# 02_IO.net
KiCad netlist of a schematic drawn in Altium Designer
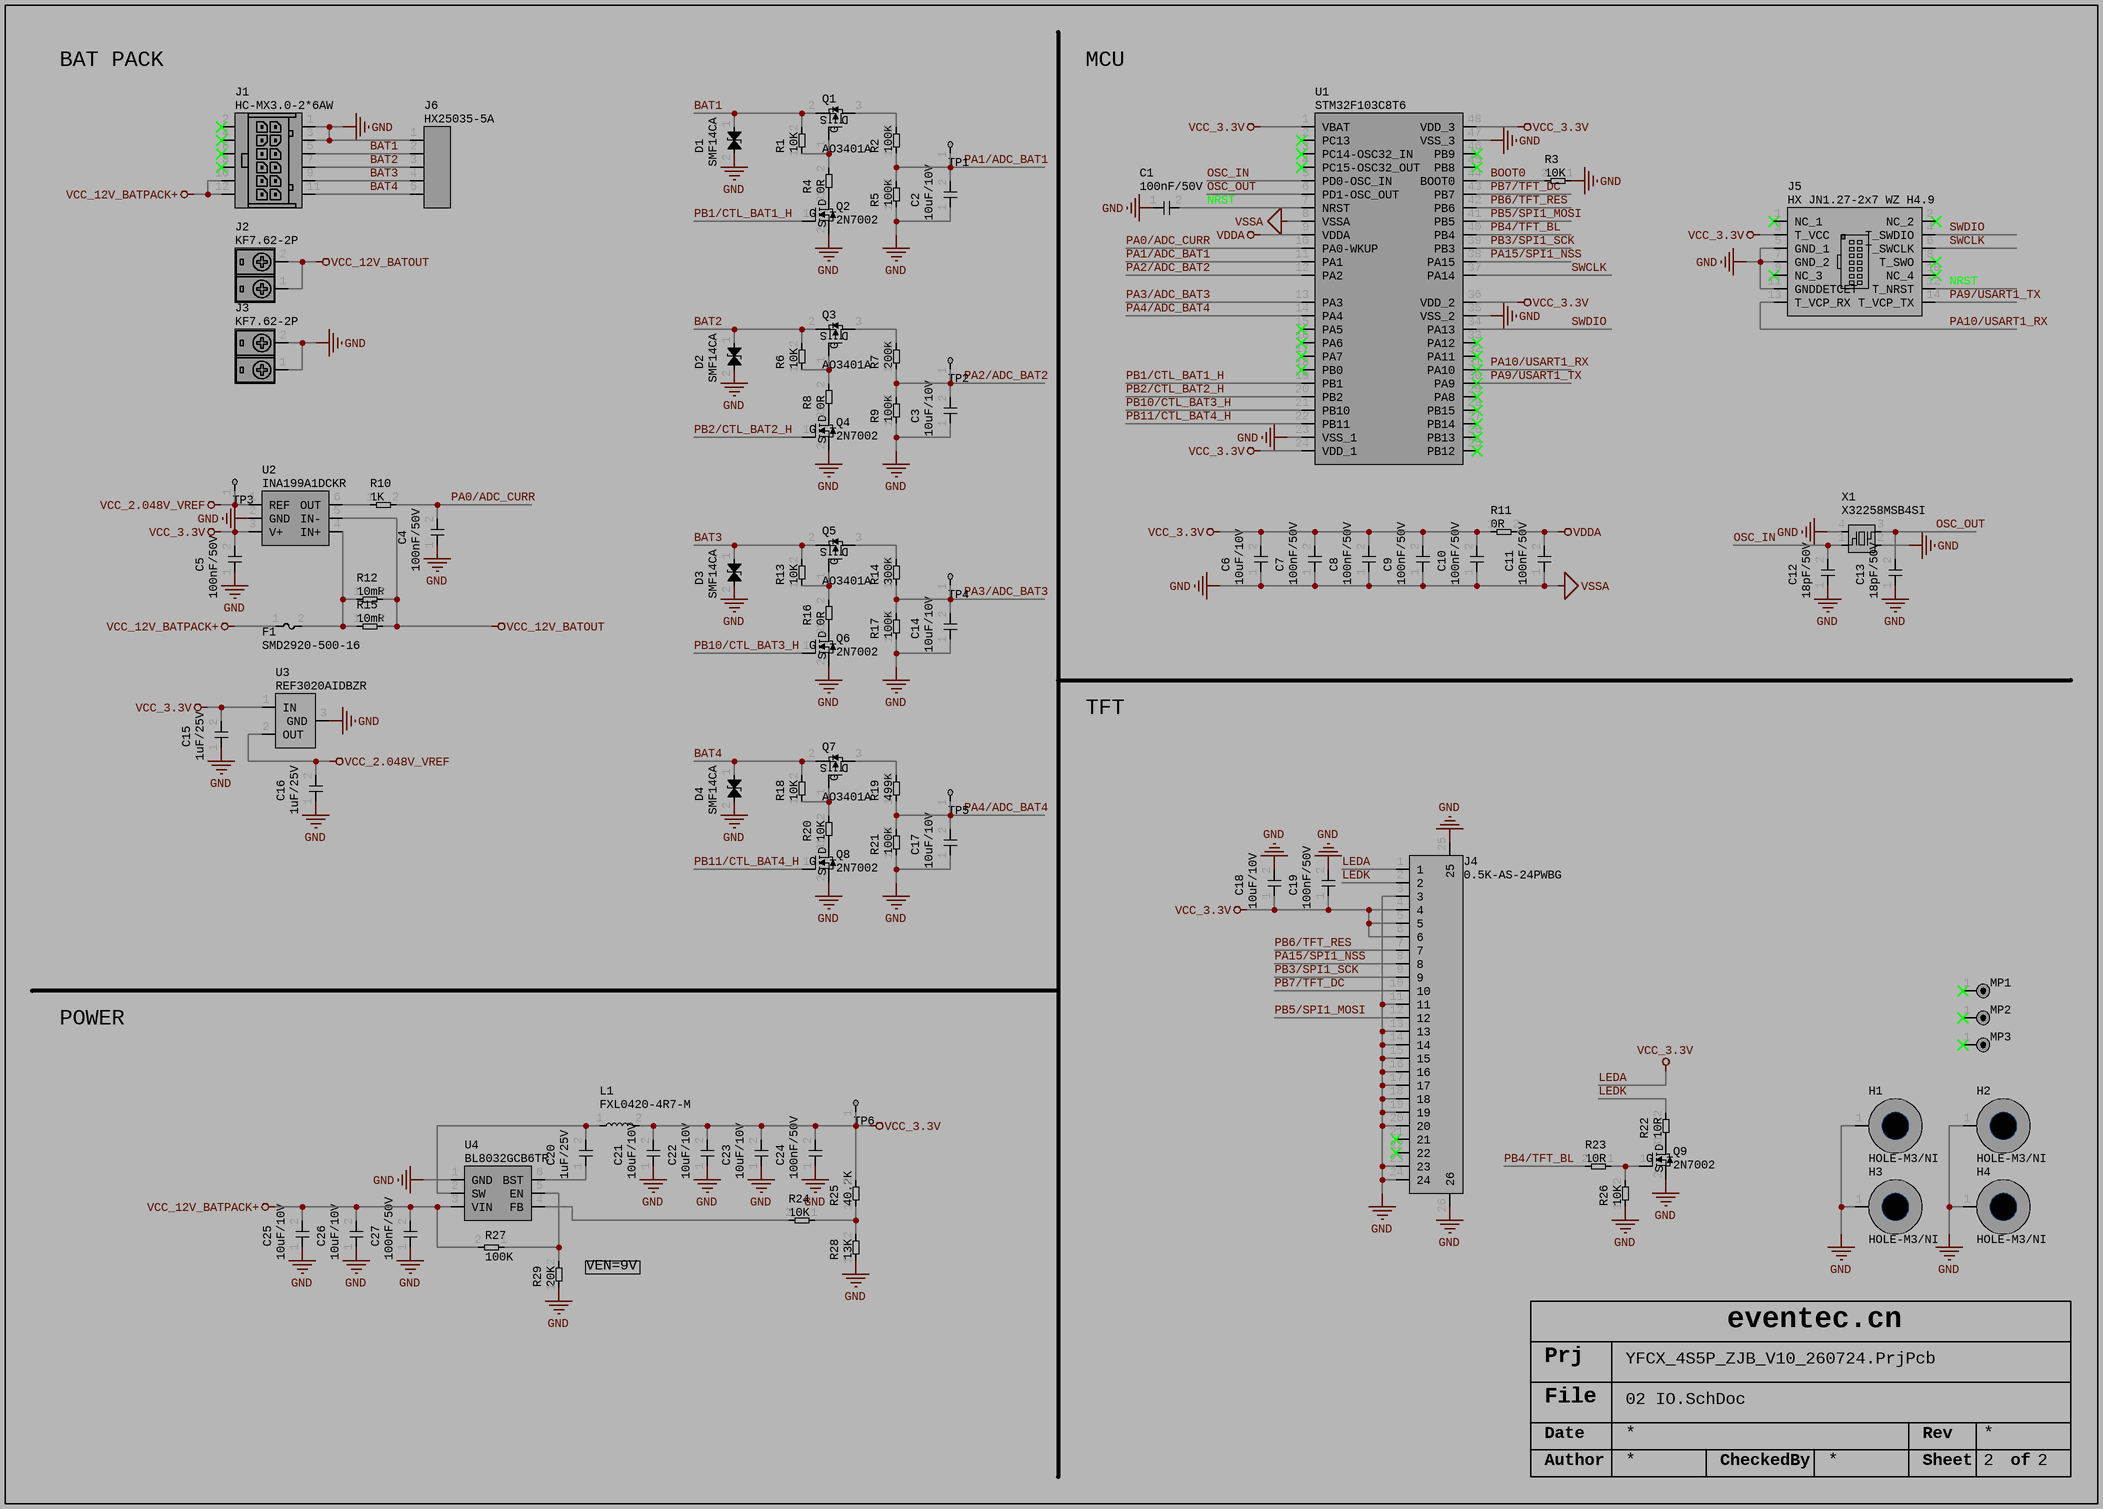
[diagram p0: 02 IO.SchDoc]

(export (version "E")
  (design (tool "Eeschema 10.0.6"))
  (components
    (comp (ref "C1") (value "100nF/50V") (footprint "C0402") (libsource (lib "YFCX") (part "100nF/50V")))
    (comp (ref "C2") (value "10uF/10V") (footprint "C0603") (libsource (lib "YFCX") (part "100nF/50V")))
    (comp (ref "C3") (value "10uF/10V") (footprint "C0603") (libsource (lib "YFCX") (part "100nF/50V")))
    (comp (ref "C4") (value "100nF/50V") (footprint "C0402") (libsource (lib "YFCX") (part "100nF/50V")))
    (comp (ref "C5") (value "100nF/50V") (footprint "C0402") (libsource (lib "YFCX") (part "100nF/50V")))
    (comp (ref "C6") (value "10uF/10V") (footprint "C0603") (libsource (lib "YFCX") (part "100nF/50V")))
    (comp (ref "C7") (value "100nF/50V") (footprint "C0402") (libsource (lib "YFCX") (part "100nF/50V")))
    (comp (ref "C8") (value "100nF/50V") (footprint "C0402") (libsource (lib "YFCX") (part "100nF/50V")))
    (comp (ref "C9") (value "100nF/50V") (footprint "C0402") (libsource (lib "YFCX") (part "100nF/50V")))
    (comp (ref "C10") (value "100nF/50V") (footprint "C0402") (libsource (lib "YFCX") (part "100nF/50V")))
    (comp (ref "C11") (value "100nF/50V") (footprint "C0402") (libsource (lib "YFCX") (part "100nF/50V")))
    (comp (ref "C12") (value "18pF/50V") (footprint "C0402") (libsource (lib "YFCX") (part "100nF/50V")))
    (comp (ref "C13") (value "18pF/50V") (footprint "C0402") (libsource (lib "YFCX") (part "100nF/50V")))
    (comp (ref "C14") (value "10uF/10V") (footprint "C0603") (libsource (lib "YFCX") (part "100nF/50V")))
    (comp (ref "C15") (value "1uF/25V") (footprint "C0402") (libsource (lib "YFCX") (part "100nF/50V")))
    (comp (ref "C16") (value "1uF/25V") (footprint "C0402") (libsource (lib "YFCX") (part "100nF/50V")))
    (comp (ref "C17") (value "10uF/10V") (footprint "C0603") (libsource (lib "YFCX") (part "100nF/50V")))
    (comp (ref "C18") (value "10uF/10V") (footprint "C0603") (libsource (lib "YFCX") (part "100nF/50V")))
    (comp (ref "C19") (value "100nF/50V") (footprint "C0402") (libsource (lib "YFCX") (part "100nF/50V")))
    (comp (ref "C20") (value "1uF/25V") (footprint "C0402") (libsource (lib "YFCX") (part "100nF/50V")))
    (comp (ref "C21") (value "10uF/10V") (footprint "C0603") (libsource (lib "YFCX") (part "100nF/50V")))
    (comp (ref "C22") (value "10uF/10V") (footprint "C0603") (libsource (lib "YFCX") (part "100nF/50V")))
    (comp (ref "C23") (value "10uF/10V") (footprint "C0603") (libsource (lib "YFCX") (part "100nF/50V")))
    (comp (ref "C24") (value "100nF/50V") (footprint "C0402") (libsource (lib "YFCX") (part "100nF/50V")))
    (comp (ref "C25") (value "10uF/10V") (footprint "C0603") (libsource (lib "YFCX") (part "100nF/50V")))
    (comp (ref "C26") (value "10uF/10V") (footprint "C0603") (libsource (lib "YFCX") (part "100nF/50V")))
    (comp (ref "C27") (value "100nF/50V") (footprint "C0402") (libsource (lib "YFCX") (part "100nF/50V")))
    (comp (ref "D1") (value "SMF14CA") (footprint "SOD123") (libsource (lib "YFCX") (part "TVS-BDIR")))
    (comp (ref "D2") (value "SMF14CA") (footprint "SOD123") (libsource (lib "YFCX") (part "TVS-BDIR")))
    (comp (ref "D3") (value "SMF14CA") (footprint "SOD123") (libsource (lib "YFCX") (part "TVS-BDIR")))
    (comp (ref "D4") (value "SMF14CA") (footprint "SOD123") (libsource (lib "YFCX") (part "TVS-BDIR")))
    (comp (ref "F1") (value "SMD2920-500-16") (footprint "FUSE2920") (libsource (lib "YFCX") (part "FUSE")))
    (comp (ref "H1")
      (value "HOLE-M3/NI")
      (footprint "HOLE6R90X3R10")
      (libsource (lib "YFCX") (part "HOLE-M3"))
    )
    (comp (ref "H2")
      (value "HOLE-M3/NI")
      (footprint "HOLE6R90X3R10")
      (libsource (lib "YFCX") (part "HOLE-M3"))
    )
    (comp (ref "H3")
      (value "HOLE-M3/NI")
      (footprint "HOLE6R90X3R10")
      (libsource (lib "YFCX") (part "HOLE-M3"))
    )
    (comp (ref "H4")
      (value "HOLE-M3/NI")
      (footprint "HOLE6R90X3R10")
      (libsource (lib "YFCX") (part "HOLE-M3"))
    )
    (comp (ref "J1")
      (value "HC-MX3.0-2*6AW")
      (footprint "HC-MX3R0-2X6AW")
      (libsource (lib "YFCX") (part "HC-MX3.0-2*6AW"))
    )
    (comp (ref "J2") (value "KF7.62-2P") (footprint "KF7R62-2P") (libsource (lib "YFCX") (part "KF7.62-2P")))
    (comp (ref "J3") (value "KF7.62-2P") (footprint "KF7R62-2P") (libsource (lib "YFCX") (part "KF7.62-2P")))
    (comp (ref "J4")
      (value "0.5K-AS-24PWBG")
      (footprint "0R5K-AS-24PWBG")
      (libsource (lib "YFCX") (part "0.5K-AS-24PWBG"))
    )
    (comp (ref "J5")
      (value "HX JN1.27-2x7 WZ H4.9")
      (footprint "STDC14-W")
      (libsource (lib "YFCX") (part "STDC14"))
    )
    (comp (ref "J6")
      (value "HX25035-5A")
      (footprint "HX25035-5A")
      (libsource (lib "YFCX") (part "HX25035-5A"))
    )
    (comp (ref "L1") (value "FXL0420-4R7-M") (footprint "L0420") (libsource (lib "YFCX") (part "INDUC")))
    (comp (ref "MP1") (value "MARK-R3/NI") (footprint "MARK-R3") (libsource (lib "YFCX") (part "MARK-R3")))
    (comp (ref "MP2") (value "MARK-R3/NI") (footprint "MARK-R3") (libsource (lib "YFCX") (part "MARK-R3")))
    (comp (ref "MP3") (value "MARK-R3/NI") (footprint "MARK-R3") (libsource (lib "YFCX") (part "MARK-R3")))
    (comp (ref "Q1") (value "AO3401A") (footprint "SOT23-3") (libsource (lib "YFCX") (part "MOS-P")))
    (comp (ref "Q2") (value "2N7002") (footprint "SOT23-3") (libsource (lib "YFCX") (part "MOS-N")))
    (comp (ref "Q3") (value "AO3401A") (footprint "SOT23-3") (libsource (lib "YFCX") (part "MOS-P")))
    (comp (ref "Q4") (value "2N7002") (footprint "SOT23-3") (libsource (lib "YFCX") (part "MOS-N")))
    (comp (ref "Q5") (value "AO3401A") (footprint "SOT23-3") (libsource (lib "YFCX") (part "MOS-P")))
    (comp (ref "Q6") (value "2N7002") (footprint "SOT23-3") (libsource (lib "YFCX") (part "MOS-N")))
    (comp (ref "Q7") (value "AO3401A") (footprint "SOT23-3") (libsource (lib "YFCX") (part "MOS-P")))
    (comp (ref "Q8") (value "2N7002") (footprint "SOT23-3") (libsource (lib "YFCX") (part "MOS-N")))
    (comp (ref "Q9") (value "2N7002") (footprint "SOT23-3") (libsource (lib "YFCX") (part "MOS-N")))
    (comp (ref "R1") (value "10K") (footprint "R0402") (libsource (lib "YFCX") (part "1K")))
    (comp (ref "R2") (value "100K") (footprint "R0402") (libsource (lib "YFCX") (part "1K")))
    (comp (ref "R3") (value "10K") (footprint "R0402") (libsource (lib "YFCX") (part "1K")))
    (comp (ref "R4") (value "0R") (footprint "R0402") (libsource (lib "YFCX") (part "1K")))
    (comp (ref "R5") (value "100K") (footprint "R0402") (libsource (lib "YFCX") (part "1K")))
    (comp (ref "R6") (value "10K") (footprint "R0402") (libsource (lib "YFCX") (part "1K")))
    (comp (ref "R7") (value "200K") (footprint "R0402") (libsource (lib "YFCX") (part "1K")))
    (comp (ref "R8") (value "0R") (footprint "R0402") (libsource (lib "YFCX") (part "1K")))
    (comp (ref "R9") (value "100K") (footprint "R0402") (libsource (lib "YFCX") (part "1K")))
    (comp (ref "R10") (value "1K") (footprint "R0402") (libsource (lib "YFCX") (part "1K")))
    (comp (ref "R11") (value "0R") (footprint "R0402") (libsource (lib "YFCX") (part "1K")))
    (comp (ref "R12") (value "10mR") (footprint "R2512") (libsource (lib "YFCX") (part "1K")))
    (comp (ref "R13") (value "10K") (footprint "R0402") (libsource (lib "YFCX") (part "1K")))
    (comp (ref "R14") (value "300K") (footprint "R0402") (libsource (lib "YFCX") (part "1K")))
    (comp (ref "R15") (value "10mR") (footprint "R2512") (libsource (lib "YFCX") (part "1K")))
    (comp (ref "R16") (value "0R") (footprint "R0402") (libsource (lib "YFCX") (part "1K")))
    (comp (ref "R17") (value "100K") (footprint "R0402") (libsource (lib "YFCX") (part "1K")))
    (comp (ref "R18") (value "10K") (footprint "R0402") (libsource (lib "YFCX") (part "1K")))
    (comp (ref "R19") (value "499K") (footprint "R0402") (libsource (lib "YFCX") (part "1K")))
    (comp (ref "R20") (value "10K") (footprint "R0402") (libsource (lib "YFCX") (part "1K")))
    (comp (ref "R21") (value "100K") (footprint "R0402") (libsource (lib "YFCX") (part "1K")))
    (comp (ref "R22") (value "10R") (footprint "R0805") (libsource (lib "YFCX") (part "1K")))
    (comp (ref "R23") (value "10R") (footprint "R0805") (libsource (lib "YFCX") (part "1K")))
    (comp (ref "R24") (value "10K") (footprint "R0402") (libsource (lib "YFCX") (part "1K")))
    (comp (ref "R25") (value "40.2K") (footprint "R0402") (libsource (lib "YFCX") (part "1K")))
    (comp (ref "R26") (value "10K") (footprint "R0402") (libsource (lib "YFCX") (part "1K")))
    (comp (ref "R27") (value "100K") (footprint "R0402") (libsource (lib "YFCX") (part "1K")))
    (comp (ref "R28") (value "13K") (footprint "R0402") (libsource (lib "YFCX") (part "1K")))
    (comp (ref "R29") (value "20K") (footprint "R0402") (libsource (lib "YFCX") (part "1K")))
    (comp (ref "TP1") (value "TP-R2/NI") (footprint "TP-R2") (libsource (lib "YFCX") (part "TP-R2")))
    (comp (ref "TP2") (value "TP-R2/NI") (footprint "TP-R2") (libsource (lib "YFCX") (part "TP-R2")))
    (comp (ref "TP3") (value "TP-R2/NI") (footprint "TP-R2") (libsource (lib "YFCX") (part "TP-R2")))
    (comp (ref "TP4") (value "TP-R2/NI") (footprint "TP-R2") (libsource (lib "YFCX") (part "TP-R2")))
    (comp (ref "TP5") (value "TP-R2/NI") (footprint "TP-R2") (libsource (lib "YFCX") (part "TP-R2")))
    (comp (ref "TP6") (value "TP-R2/NI") (footprint "TP-R2") (libsource (lib "YFCX") (part "TP-R2")))
    (comp (ref "U1")
      (value "STM32F103C8T6")
      (footprint "LQFP48-7X7X0R5")
      (libsource (lib "MyIC") (part "STM32F103C8T6"))
    )
    (comp (ref "U2")
      (value "INA199A1DCKR")
      (footprint "SOT363")
      (libsource (lib "MyIC") (part "INA199A1DCKR"))
    )
    (comp (ref "U3")
      (value "REF3020AIDBZR")
      (footprint "SOT23-3")
      (libsource (lib "MyIC") (part "REF3020AIDBZR"))
    )
    (comp (ref "U4")
      (value "BL8032GCB6TR")
      (footprint "SOT23-6")
      (libsource (lib "MyIC") (part "BL8032GCB6TR"))
    )
    (comp (ref "X1")
      (value "X32258MSB4SI")
      (footprint "X-4P-3R2X2R5-SMD")
      (libsource (lib "YFCX") (part "XTAL"))
    )
  )
  (nets
    (net (code "1") (name "/BAT1") (class "Default")
      (node (ref "D1") (pin "1") (pinfunction "1_1") (pintype "passive"))
      (node (ref "J1") (pin "5") (pinfunction "5_5") (pintype "passive"))
      (node (ref "J6") (pin "2") (pinfunction "2_2") (pintype "passive"))
      (node (ref "Q1") (pin "2") (pinfunction "S_2") (pintype "passive"))
      (node (ref "R1") (pin "2") (pinfunction "2_2") (pintype "passive"))
    )
    (net (code "2") (name "/BAT2") (class "Default")
      (node (ref "D2") (pin "1") (pinfunction "1_1") (pintype "passive"))
      (node (ref "J1") (pin "7") (pinfunction "7_7") (pintype "passive"))
      (node (ref "J6") (pin "3") (pinfunction "3_3") (pintype "passive"))
      (node (ref "Q3") (pin "2") (pinfunction "S_2") (pintype "passive"))
      (node (ref "R6") (pin "2") (pinfunction "2_2") (pintype "passive"))
    )
    (net (code "3") (name "/BAT3") (class "Default")
      (node (ref "D3") (pin "1") (pinfunction "1_1") (pintype "passive"))
      (node (ref "J1") (pin "9") (pinfunction "9_9") (pintype "passive"))
      (node (ref "J6") (pin "4") (pinfunction "4_4") (pintype "passive"))
      (node (ref "Q5") (pin "2") (pinfunction "S_2") (pintype "passive"))
      (node (ref "R13") (pin "2") (pinfunction "2_2") (pintype "passive"))
    )
    (net (code "4") (name "/BAT4") (class "Default")
      (node (ref "D4") (pin "1") (pinfunction "1_1") (pintype "passive"))
      (node (ref "J1") (pin "11") (pinfunction "11_11") (pintype "passive"))
      (node (ref "J6") (pin "5") (pinfunction "5_5") (pintype "passive"))
      (node (ref "Q7") (pin "2") (pinfunction "S_2") (pintype "passive"))
      (node (ref "R18") (pin "2") (pinfunction "2_2") (pintype "passive"))
    )
    (net (code "5") (name "/BOOT0") (class "Default")
      (node (ref "R3") (pin "2") (pinfunction "2_2") (pintype "passive"))
      (node (ref "U1") (pin "44") (pinfunction "BOOT0_44") (pintype "passive"))
    )
    (net (code "6") (name "/LEDK") (class "Default")
      (node (ref "J4") (pin "2") (pinfunction "2_2") (pintype "passive"))
      (node (ref "R22") (pin "2") (pinfunction "2_2") (pintype "passive"))
    )
    (net (code "7") (name "/NRST") (class "Default")
      (node (ref "C1") (pin "2") (pinfunction "2_2") (pintype "passive"))
      (node (ref "J5") (pin "12") (pinfunction "T_NRST_12") (pintype "passive"))
      (node (ref "U1") (pin "7") (pinfunction "NRST_7") (pintype "passive"))
    )
    (net (code "8") (name "/OSC_IN") (class "Default")
      (node (ref "C12") (pin "2") (pinfunction "2_2") (pintype "passive"))
      (node (ref "U1") (pin "5") (pinfunction "PD0-OSC_IN_5") (pintype "passive"))
      (node (ref "X1") (pin "1") (pinfunction "1_1") (pintype "passive"))
    )
    (net (code "9") (name "/OSC_OUT") (class "Default")
      (node (ref "C13") (pin "2") (pinfunction "2_2") (pintype "passive"))
      (node (ref "U1") (pin "6") (pinfunction "PD1-OSC_OUT_6") (pintype "passive"))
      (node (ref "X1") (pin "3") (pinfunction "3_3") (pintype "passive"))
    )
    (net (code "10") (name "/PA0{slash}ADC_CURR") (class "Default")
      (node (ref "C4") (pin "2") (pinfunction "2_2") (pintype "passive"))
      (node (ref "R10") (pin "2") (pinfunction "2_2") (pintype "passive"))
      (node (ref "U1") (pin "10") (pinfunction "PA0-WKUP_10") (pintype "passive"))
    )
    (net (code "11") (name "/PA1{slash}ADC_BAT1") (class "Default")
      (node (ref "C2") (pin "2") (pinfunction "2_2") (pintype "passive"))
      (node (ref "R2") (pin "1") (pinfunction "1_1") (pintype "passive"))
      (node (ref "R5") (pin "2") (pinfunction "2_2") (pintype "passive"))
      (node (ref "TP1") (pin "1") (pinfunction "1_1") (pintype "passive"))
      (node (ref "U1") (pin "11") (pinfunction "PA1_11") (pintype "passive"))
    )
    (net (code "12") (name "/PA2{slash}ADC_BAT2") (class "Default")
      (node (ref "C3") (pin "2") (pinfunction "2_2") (pintype "passive"))
      (node (ref "R7") (pin "1") (pinfunction "1_1") (pintype "passive"))
      (node (ref "R9") (pin "2") (pinfunction "2_2") (pintype "passive"))
      (node (ref "TP2") (pin "1") (pinfunction "1_1") (pintype "passive"))
      (node (ref "U1") (pin "12") (pinfunction "PA2_12") (pintype "passive"))
    )
    (net (code "13") (name "/PA3{slash}ADC_BAT3") (class "Default")
      (node (ref "C14") (pin "2") (pinfunction "2_2") (pintype "passive"))
      (node (ref "R14") (pin "1") (pinfunction "1_1") (pintype "passive"))
      (node (ref "R17") (pin "2") (pinfunction "2_2") (pintype "passive"))
      (node (ref "TP4") (pin "1") (pinfunction "1_1") (pintype "passive"))
      (node (ref "U1") (pin "13") (pinfunction "PA3_13") (pintype "passive"))
    )
    (net (code "14") (name "/PA4{slash}ADC_BAT4") (class "Default")
      (node (ref "C17") (pin "2") (pinfunction "2_2") (pintype "passive"))
      (node (ref "R19") (pin "1") (pinfunction "1_1") (pintype "passive"))
      (node (ref "R21") (pin "2") (pinfunction "2_2") (pintype "passive"))
      (node (ref "TP5") (pin "1") (pinfunction "1_1") (pintype "passive"))
      (node (ref "U1") (pin "14") (pinfunction "PA4_14") (pintype "passive"))
    )
    (net (code "15") (name "/PA9{slash}USART1_TX") (class "Default")
      (node (ref "J5") (pin "14") (pinfunction "T_VCP_TX_14") (pintype "passive"))
      (node (ref "U1") (pin "30") (pinfunction "PA9_30") (pintype "passive"))
    )
    (net (code "16") (name "/PA10{slash}USART1_RX") (class "Default")
      (node (ref "J5") (pin "13") (pinfunction "T_VCP_RX_13") (pintype "passive"))
      (node (ref "U1") (pin "31") (pinfunction "PA10_31") (pintype "passive"))
    )
    (net (code "17") (name "/PA15{slash}SPI1_NSS") (class "Default")
      (node (ref "J4") (pin "8") (pinfunction "8_8") (pintype "passive"))
      (node (ref "U1") (pin "38") (pinfunction "PA15_38") (pintype "passive"))
    )
    (net (code "18") (name "/PB1{slash}CTL_BAT1_H") (class "Default")
      (node (ref "Q2") (pin "1") (pinfunction "G_1") (pintype "passive"))
      (node (ref "U1") (pin "19") (pinfunction "PB1_19") (pintype "passive"))
    )
    (net (code "19") (name "/PB2{slash}CTL_BAT2_H") (class "Default")
      (node (ref "Q4") (pin "1") (pinfunction "G_1") (pintype "passive"))
      (node (ref "U1") (pin "20") (pinfunction "PB2_20") (pintype "passive"))
    )
    (net (code "20") (name "/PB3{slash}SPI1_SCK") (class "Default")
      (node (ref "J4") (pin "9") (pinfunction "9_9") (pintype "passive"))
      (node (ref "U1") (pin "39") (pinfunction "PB3_39") (pintype "passive"))
    )
    (net (code "21") (name "/PB4{slash}TFT_BL") (class "Default")
      (node (ref "R23") (pin "2") (pinfunction "2_2") (pintype "passive"))
      (node (ref "U1") (pin "40") (pinfunction "PB4_40") (pintype "passive"))
    )
    (net (code "22") (name "/PB5{slash}SPI1_MOSI") (class "Default")
      (node (ref "J4") (pin "12") (pinfunction "12_12") (pintype "passive"))
      (node (ref "U1") (pin "41") (pinfunction "PB5_41") (pintype "passive"))
    )
    (net (code "23") (name "/PB6{slash}TFT_RES") (class "Default")
      (node (ref "J4") (pin "7") (pinfunction "7_7") (pintype "passive"))
      (node (ref "U1") (pin "42") (pinfunction "PB6_42") (pintype "passive"))
    )
    (net (code "24") (name "/PB7{slash}TFT_DC") (class "Default")
      (node (ref "J4") (pin "10") (pinfunction "10_10") (pintype "passive"))
      (node (ref "U1") (pin "43") (pinfunction "PB7_43") (pintype "passive"))
    )
    (net (code "25") (name "/PB10{slash}CTL_BAT3_H") (class "Default")
      (node (ref "Q6") (pin "1") (pinfunction "G_1") (pintype "passive"))
      (node (ref "U1") (pin "21") (pinfunction "PB10_21") (pintype "passive"))
    )
    (net (code "26") (name "/PB11{slash}CTL_BAT4_H") (class "Default")
      (node (ref "Q8") (pin "1") (pinfunction "G_1") (pintype "passive"))
      (node (ref "U1") (pin "22") (pinfunction "PB11_22") (pintype "passive"))
    )
    (net (code "27") (name "/SWCLK") (class "Default")
      (node (ref "J5") (pin "6") (pinfunction "T_SWCLK_6") (pintype "passive"))
      (node (ref "U1") (pin "37") (pinfunction "PA14_37") (pintype "passive"))
    )
    (net (code "28") (name "/SWDIO") (class "Default")
      (node (ref "J5") (pin "4") (pinfunction "T_SWDIO_4") (pintype "passive"))
      (node (ref "U1") (pin "34") (pinfunction "PA13_34") (pintype "passive"))
    )
    (net (code "29") (name "GND") (class "Default")
      (node (ref "C1") (pin "1") (pinfunction "1_1") (pintype "passive"))
      (node (ref "C10") (pin "1") (pinfunction "1_1") (pintype "passive"))
      (node (ref "C11") (pin "1") (pinfunction "1_1") (pintype "passive"))
      (node (ref "C12") (pin "1") (pinfunction "1_1") (pintype "passive"))
      (node (ref "C13") (pin "1") (pinfunction "1_1") (pintype "passive"))
      (node (ref "C14") (pin "1") (pinfunction "1_1") (pintype "passive"))
      (node (ref "C15") (pin "1") (pinfunction "1_1") (pintype "passive"))
      (node (ref "C16") (pin "1") (pinfunction "1_1") (pintype "passive"))
      (node (ref "C17") (pin "1") (pinfunction "1_1") (pintype "passive"))
      (node (ref "C18") (pin "2") (pinfunction "2_2") (pintype "passive"))
      (node (ref "C19") (pin "2") (pinfunction "2_2") (pintype "passive"))
      (node (ref "C2") (pin "1") (pinfunction "1_1") (pintype "passive"))
      (node (ref "C21") (pin "1") (pinfunction "1_1") (pintype "passive"))
      (node (ref "C22") (pin "1") (pinfunction "1_1") (pintype "passive"))
      (node (ref "C23") (pin "1") (pinfunction "1_1") (pintype "passive"))
      (node (ref "C24") (pin "1") (pinfunction "1_1") (pintype "passive"))
      (node (ref "C25") (pin "1") (pinfunction "1_1") (pintype "passive"))
      (node (ref "C26") (pin "1") (pinfunction "1_1") (pintype "passive"))
      (node (ref "C27") (pin "1") (pinfunction "1_1") (pintype "passive"))
      (node (ref "C3") (pin "1") (pinfunction "1_1") (pintype "passive"))
      (node (ref "C4") (pin "1") (pinfunction "1_1") (pintype "passive"))
      (node (ref "C5") (pin "1") (pinfunction "1_1") (pintype "passive"))
      (node (ref "C6") (pin "1") (pinfunction "1_1") (pintype "passive"))
      (node (ref "C7") (pin "1") (pinfunction "1_1") (pintype "passive"))
      (node (ref "C8") (pin "1") (pinfunction "1_1") (pintype "passive"))
      (node (ref "C9") (pin "1") (pinfunction "1_1") (pintype "passive"))
      (node (ref "D1") (pin "2") (pinfunction "2_2") (pintype "passive"))
      (node (ref "D2") (pin "2") (pinfunction "2_2") (pintype "passive"))
      (node (ref "D3") (pin "2") (pinfunction "2_2") (pintype "passive"))
      (node (ref "D4") (pin "2") (pinfunction "2_2") (pintype "passive"))
      (node (ref "H1") (pin "1") (pinfunction "1_1") (pintype "passive"))
      (node (ref "H2") (pin "1") (pinfunction "1_1") (pintype "passive"))
      (node (ref "H3") (pin "1") (pinfunction "1_1") (pintype "passive"))
      (node (ref "H4") (pin "1") (pinfunction "1_1") (pintype "passive"))
      (node (ref "J1") (pin "1") (pinfunction "1_1") (pintype "passive"))
      (node (ref "J1") (pin "3") (pinfunction "3_3") (pintype "passive"))
      (node (ref "J3") (pin "1") (pinfunction "1_1") (pintype "passive"))
      (node (ref "J3") (pin "2") (pinfunction "2_2") (pintype "passive"))
      (node (ref "J4") (pin "11") (pinfunction "11_11") (pintype "passive"))
      (node (ref "J4") (pin "13") (pinfunction "13_13") (pintype "passive"))
      (node (ref "J4") (pin "14") (pinfunction "14_14") (pintype "passive"))
      (node (ref "J4") (pin "15") (pinfunction "15_15") (pintype "passive"))
      (node (ref "J4") (pin "16") (pinfunction "16_16") (pintype "passive"))
      (node (ref "J4") (pin "17") (pinfunction "17_17") (pintype "passive"))
      (node (ref "J4") (pin "18") (pinfunction "18_18") (pintype "passive"))
      (node (ref "J4") (pin "19") (pinfunction "19_19") (pintype "passive"))
      (node (ref "J4") (pin "20") (pinfunction "20_20") (pintype "passive"))
      (node (ref "J4") (pin "23") (pinfunction "23_23") (pintype "passive"))
      (node (ref "J4") (pin "24") (pinfunction "24_24") (pintype "passive"))
      (node (ref "J4") (pin "25") (pinfunction "25_25") (pintype "passive"))
      (node (ref "J4") (pin "26") (pinfunction "26_26") (pintype "passive"))
      (node (ref "J4") (pin "3") (pinfunction "3_3") (pintype "passive"))
      (node (ref "J5") (pin "11") (pinfunction "GNDDETCET_11") (pintype "passive"))
      (node (ref "J5") (pin "5") (pinfunction "GND_1_5") (pintype "passive"))
      (node (ref "J5") (pin "7") (pinfunction "GND_2_7") (pintype "passive"))
      (node (ref "J6") (pin "1") (pinfunction "1_1") (pintype "passive"))
      (node (ref "Q2") (pin "2") (pinfunction "S_2") (pintype "passive"))
      (node (ref "Q4") (pin "2") (pinfunction "S_2") (pintype "passive"))
      (node (ref "Q6") (pin "2") (pinfunction "S_2") (pintype "passive"))
      (node (ref "Q8") (pin "2") (pinfunction "S_2") (pintype "passive"))
      (node (ref "Q9") (pin "2") (pinfunction "S_2") (pintype "passive"))
      (node (ref "R17") (pin "1") (pinfunction "1_1") (pintype "passive"))
      (node (ref "R21") (pin "1") (pinfunction "1_1") (pintype "passive"))
      (node (ref "R26") (pin "1") (pinfunction "1_1") (pintype "passive"))
      (node (ref "R28") (pin "1") (pinfunction "1_1") (pintype "passive"))
      (node (ref "R29") (pin "1") (pinfunction "1_1") (pintype "passive"))
      (node (ref "R3") (pin "1") (pinfunction "1_1") (pintype "passive"))
      (node (ref "R5") (pin "1") (pinfunction "1_1") (pintype "passive"))
      (node (ref "R9") (pin "1") (pinfunction "1_1") (pintype "passive"))
      (node (ref "U1") (pin "23") (pinfunction "VSS_1_23") (pintype "passive"))
      (node (ref "U1") (pin "35") (pinfunction "VSS_2_35") (pintype "passive"))
      (node (ref "U1") (pin "47") (pinfunction "VSS_3_47") (pintype "passive"))
      (node (ref "U1") (pin "8") (pinfunction "VSSA_8") (pintype "passive"))
      (node (ref "U2") (pin "2") (pinfunction "GND_2") (pintype "passive"))
      (node (ref "U3") (pin "3") (pinfunction "GND_3") (pintype "passive"))
      (node (ref "U4") (pin "1") (pinfunction "GND_1") (pintype "passive"))
      (node (ref "X1") (pin "2") (pinfunction "2_2") (pintype "passive"))
      (node (ref "X1") (pin "4") (pinfunction "4_4") (pintype "passive"))
    )
    (net (code "30") (name "Net-(Q1-D)") (class "Default")
      (node (ref "Q1") (pin "3") (pinfunction "D_3") (pintype "passive"))
      (node (ref "R2") (pin "2") (pinfunction "2_2") (pintype "passive"))
    )
    (net (code "31") (name "Net-(Q1-G)") (class "Default")
      (node (ref "Q1") (pin "1") (pinfunction "G_1") (pintype "passive"))
      (node (ref "R1") (pin "1") (pinfunction "1_1") (pintype "passive"))
      (node (ref "R4") (pin "2") (pinfunction "2_2") (pintype "passive"))
    )
    (net (code "32") (name "Net-(Q2-D)") (class "Default")
      (node (ref "Q2") (pin "3") (pinfunction "D_3") (pintype "passive"))
      (node (ref "R4") (pin "1") (pinfunction "1_1") (pintype "passive"))
    )
    (net (code "33") (name "Net-(Q3-D)") (class "Default")
      (node (ref "Q3") (pin "3") (pinfunction "D_3") (pintype "passive"))
      (node (ref "R7") (pin "2") (pinfunction "2_2") (pintype "passive"))
    )
    (net (code "34") (name "Net-(Q3-G)") (class "Default")
      (node (ref "Q3") (pin "1") (pinfunction "G_1") (pintype "passive"))
      (node (ref "R6") (pin "1") (pinfunction "1_1") (pintype "passive"))
      (node (ref "R8") (pin "2") (pinfunction "2_2") (pintype "passive"))
    )
    (net (code "35") (name "Net-(Q4-D)") (class "Default")
      (node (ref "Q4") (pin "3") (pinfunction "D_3") (pintype "passive"))
      (node (ref "R8") (pin "1") (pinfunction "1_1") (pintype "passive"))
    )
    (net (code "36") (name "Net-(Q5-D)") (class "Default")
      (node (ref "Q5") (pin "3") (pinfunction "D_3") (pintype "passive"))
      (node (ref "R14") (pin "2") (pinfunction "2_2") (pintype "passive"))
    )
    (net (code "37") (name "Net-(Q5-G)") (class "Default")
      (node (ref "Q5") (pin "1") (pinfunction "G_1") (pintype "passive"))
      (node (ref "R13") (pin "1") (pinfunction "1_1") (pintype "passive"))
      (node (ref "R16") (pin "2") (pinfunction "2_2") (pintype "passive"))
    )
    (net (code "38") (name "Net-(Q6-D)") (class "Default")
      (node (ref "Q6") (pin "3") (pinfunction "D_3") (pintype "passive"))
      (node (ref "R16") (pin "1") (pinfunction "1_1") (pintype "passive"))
    )
    (net (code "39") (name "Net-(Q7-D)") (class "Default")
      (node (ref "Q7") (pin "3") (pinfunction "D_3") (pintype "passive"))
      (node (ref "R19") (pin "2") (pinfunction "2_2") (pintype "passive"))
    )
    (net (code "40") (name "Net-(Q7-G)") (class "Default")
      (node (ref "Q7") (pin "1") (pinfunction "G_1") (pintype "passive"))
      (node (ref "R18") (pin "1") (pinfunction "1_1") (pintype "passive"))
      (node (ref "R20") (pin "2") (pinfunction "2_2") (pintype "passive"))
    )
    (net (code "41") (name "Net-(Q8-D)") (class "Default")
      (node (ref "Q8") (pin "3") (pinfunction "D_3") (pintype "passive"))
      (node (ref "R20") (pin "1") (pinfunction "1_1") (pintype "passive"))
    )
    (net (code "42") (name "Net-(Q9-D)") (class "Default")
      (node (ref "Q9") (pin "3") (pinfunction "D_3") (pintype "passive"))
      (node (ref "R22") (pin "1") (pinfunction "1_1") (pintype "passive"))
    )
    (net (code "43") (name "Net-(Q9-G)") (class "Default")
      (node (ref "Q9") (pin "1") (pinfunction "G_1") (pintype "passive"))
      (node (ref "R23") (pin "1") (pinfunction "1_1") (pintype "passive"))
      (node (ref "R26") (pin "2") (pinfunction "2_2") (pintype "passive"))
    )
    (net (code "44") (name "Net-(R24-Pad1)") (class "Default")
      (node (ref "R24") (pin "1") (pinfunction "1_1") (pintype "passive"))
      (node (ref "R25") (pin "1") (pinfunction "1_1") (pintype "passive"))
      (node (ref "R28") (pin "2") (pinfunction "2_2") (pintype "passive"))
    )
    (net (code "45") (name "Net-(U2-IN+)") (class "Default")
      (node (ref "F1") (pin "2") (pinfunction "2_2") (pintype "passive"))
      (node (ref "R12") (pin "1") (pinfunction "1_1") (pintype "passive"))
      (node (ref "R15") (pin "1") (pinfunction "1_1") (pintype "passive"))
      (node (ref "U2") (pin "4") (pinfunction "IN+_4") (pintype "passive"))
    )
    (net (code "46") (name "Net-(U2-OUT)") (class "Default")
      (node (ref "R10") (pin "1") (pinfunction "1_1") (pintype "passive"))
      (node (ref "U2") (pin "6") (pinfunction "OUT_6") (pintype "passive"))
    )
    (net (code "47") (name "Net-(U4-BST)") (class "Default")
      (node (ref "C20") (pin "1") (pinfunction "1_1") (pintype "passive"))
      (node (ref "U4") (pin "6") (pinfunction "BST_6") (pintype "passive"))
    )
    (net (code "48") (name "Net-(U4-EN)") (class "Default")
      (node (ref "R27") (pin "1") (pinfunction "1_1") (pintype "passive"))
      (node (ref "R29") (pin "2") (pinfunction "2_2") (pintype "passive"))
      (node (ref "U4") (pin "5") (pinfunction "EN_5") (pintype "passive"))
    )
    (net (code "49") (name "Net-(U4-FB)") (class "Default")
      (node (ref "R24") (pin "2") (pinfunction "2_2") (pintype "passive"))
      (node (ref "U4") (pin "4") (pinfunction "FB_4") (pintype "passive"))
    )
    (net (code "50") (name "Net-(U4-SW)") (class "Default")
      (node (ref "C20") (pin "2") (pinfunction "2_2") (pintype "passive"))
      (node (ref "L1") (pin "1") (pinfunction "1_1") (pintype "passive"))
      (node (ref "U4") (pin "2") (pinfunction "SW_2") (pintype "passive"))
    )
    (net (code "51") (name "VCC_2.048V_VREF") (class "Default")
      (node (ref "C16") (pin "2") (pinfunction "2_2") (pintype "passive"))
      (node (ref "TP3") (pin "1") (pinfunction "1_1") (pintype "passive"))
      (node (ref "U2") (pin "1") (pinfunction "REF_1") (pintype "passive"))
      (node (ref "U3") (pin "2") (pinfunction "OUT_2") (pintype "passive"))
    )
    (net (code "52") (name "VCC_3.3V") (class "Default")
      (node (ref "C10") (pin "2") (pinfunction "2_2") (pintype "passive"))
      (node (ref "C15") (pin "2") (pinfunction "2_2") (pintype "passive"))
      (node (ref "C18") (pin "1") (pinfunction "1_1") (pintype "passive"))
      (node (ref "C19") (pin "1") (pinfunction "1_1") (pintype "passive"))
      (node (ref "C21") (pin "2") (pinfunction "2_2") (pintype "passive"))
      (node (ref "C22") (pin "2") (pinfunction "2_2") (pintype "passive"))
      (node (ref "C23") (pin "2") (pinfunction "2_2") (pintype "passive"))
      (node (ref "C24") (pin "2") (pinfunction "2_2") (pintype "passive"))
      (node (ref "C5") (pin "2") (pinfunction "2_2") (pintype "passive"))
      (node (ref "C6") (pin "2") (pinfunction "2_2") (pintype "passive"))
      (node (ref "C7") (pin "2") (pinfunction "2_2") (pintype "passive"))
      (node (ref "C8") (pin "2") (pinfunction "2_2") (pintype "passive"))
      (node (ref "C9") (pin "2") (pinfunction "2_2") (pintype "passive"))
      (node (ref "J4") (pin "1") (pinfunction "1_1") (pintype "passive"))
      (node (ref "J4") (pin "4") (pinfunction "4_4") (pintype "passive"))
      (node (ref "J4") (pin "5") (pinfunction "5_5") (pintype "passive"))
      (node (ref "J4") (pin "6") (pinfunction "6_6") (pintype "passive"))
      (node (ref "J5") (pin "3") (pinfunction "T_VCC_3") (pintype "passive"))
      (node (ref "L1") (pin "2") (pinfunction "2_2") (pintype "passive"))
      (node (ref "R11") (pin "1") (pinfunction "1_1") (pintype "passive"))
      (node (ref "R25") (pin "2") (pinfunction "2_2") (pintype "passive"))
      (node (ref "TP6") (pin "1") (pinfunction "1_1") (pintype "passive"))
      (node (ref "U1") (pin "1") (pinfunction "VBAT_1") (pintype "passive"))
      (node (ref "U1") (pin "24") (pinfunction "VDD_1_24") (pintype "passive"))
      (node (ref "U1") (pin "36") (pinfunction "VDD_2_36") (pintype "passive"))
      (node (ref "U1") (pin "48") (pinfunction "VDD_3_48") (pintype "passive"))
      (node (ref "U2") (pin "3") (pinfunction "V+_3") (pintype "passive"))
      (node (ref "U3") (pin "1") (pinfunction "IN_1") (pintype "passive"))
    )
    (net (code "53") (name "VCC_12V_BATOUT") (class "Default")
      (node (ref "J2") (pin "1") (pinfunction "1_1") (pintype "passive"))
      (node (ref "J2") (pin "2") (pinfunction "2_2") (pintype "passive"))
      (node (ref "R12") (pin "2") (pinfunction "2_2") (pintype "passive"))
      (node (ref "R15") (pin "2") (pinfunction "2_2") (pintype "passive"))
      (node (ref "U2") (pin "5") (pinfunction "IN-_5") (pintype "passive"))
    )
    (net (code "54") (name "VCC_12V_BATPACK+") (class "Default")
      (node (ref "C25") (pin "2") (pinfunction "2_2") (pintype "passive"))
      (node (ref "C26") (pin "2") (pinfunction "2_2") (pintype "passive"))
      (node (ref "C27") (pin "2") (pinfunction "2_2") (pintype "passive"))
      (node (ref "F1") (pin "1") (pinfunction "1_1") (pintype "passive"))
      (node (ref "J1") (pin "10") (pinfunction "10_10") (pintype "passive"))
      (node (ref "J1") (pin "12") (pinfunction "12_12") (pintype "passive"))
      (node (ref "R27") (pin "2") (pinfunction "2_2") (pintype "passive"))
      (node (ref "U4") (pin "3") (pinfunction "VIN_3") (pintype "passive"))
    )
    (net (code "55") (name "VDDA") (class "Default")
      (node (ref "C11") (pin "2") (pinfunction "2_2") (pintype "passive"))
      (node (ref "R11") (pin "2") (pinfunction "2_2") (pintype "passive"))
      (node (ref "U1") (pin "9") (pinfunction "VDDA_9") (pintype "passive"))
    )
    (net (code "56") (name "unconnected-(J1-Pad2)") (class "Default")
      (node (ref "J1") (pin "2") (pinfunction "2_2") (pintype "passive+no_connect"))
    )
    (net (code "57") (name "unconnected-(J1-Pad4)") (class "Default")
      (node (ref "J1") (pin "4") (pinfunction "4_4") (pintype "passive+no_connect"))
    )
    (net (code "58") (name "unconnected-(J1-Pad6)") (class "Default")
      (node (ref "J1") (pin "6") (pinfunction "6_6") (pintype "passive+no_connect"))
    )
    (net (code "59") (name "unconnected-(J1-Pad8)") (class "Default")
      (node (ref "J1") (pin "8") (pinfunction "8_8") (pintype "passive+no_connect"))
    )
    (net (code "60") (name "unconnected-(J4-Pad21)") (class "Default")
      (node (ref "J4") (pin "21") (pinfunction "21_21") (pintype "passive+no_connect"))
    )
    (net (code "61") (name "unconnected-(J4-Pad22)") (class "Default")
      (node (ref "J4") (pin "22") (pinfunction "22_22") (pintype "passive+no_connect"))
    )
    (net (code "62") (name "unconnected-(J5-NC_1-Pad1)") (class "Default")
      (node (ref "J5") (pin "1") (pinfunction "NC_1_1") (pintype "passive+no_connect"))
    )
    (net (code "63") (name "unconnected-(J5-NC_2-Pad2)") (class "Default")
      (node (ref "J5") (pin "2") (pinfunction "NC_2_2") (pintype "passive+no_connect"))
    )
    (net (code "64") (name "unconnected-(J5-NC_3-Pad9)") (class "Default")
      (node (ref "J5") (pin "9") (pinfunction "NC_3_9") (pintype "passive+no_connect"))
    )
    (net (code "65") (name "unconnected-(J5-NC_4-Pad10)") (class "Default")
      (node (ref "J5") (pin "10") (pinfunction "NC_4_10") (pintype "passive+no_connect"))
    )
    (net (code "66") (name "unconnected-(J5-T_SWO-Pad8)") (class "Default")
      (node (ref "J5") (pin "8") (pinfunction "T_SWO_8") (pintype "passive+no_connect"))
    )
    (net (code "67") (name "unconnected-(MP1-Pad1)") (class "Default")
      (node (ref "MP1") (pin "1") (pinfunction "1_1") (pintype "passive+no_connect"))
    )
    (net (code "68") (name "unconnected-(MP2-Pad1)") (class "Default")
      (node (ref "MP2") (pin "1") (pinfunction "1_1") (pintype "passive+no_connect"))
    )
    (net (code "69") (name "unconnected-(MP3-Pad1)") (class "Default")
      (node (ref "MP3") (pin "1") (pinfunction "1_1") (pintype "passive+no_connect"))
    )
    (net (code "70") (name "unconnected-(U1-PA5-Pad15)") (class "Default")
      (node (ref "U1") (pin "15") (pinfunction "PA5_15") (pintype "passive+no_connect"))
    )
    (net (code "71") (name "unconnected-(U1-PA6-Pad16)") (class "Default")
      (node (ref "U1") (pin "16") (pinfunction "PA6_16") (pintype "passive+no_connect"))
    )
    (net (code "72") (name "unconnected-(U1-PA7-Pad17)") (class "Default")
      (node (ref "U1") (pin "17") (pinfunction "PA7_17") (pintype "passive+no_connect"))
    )
    (net (code "73") (name "unconnected-(U1-PA8-Pad29)") (class "Default")
      (node (ref "U1") (pin "29") (pinfunction "PA8_29") (pintype "passive+no_connect"))
    )
    (net (code "74") (name "unconnected-(U1-PA11-Pad32)") (class "Default")
      (node (ref "U1") (pin "32") (pinfunction "PA11_32") (pintype "passive+no_connect"))
    )
    (net (code "75") (name "unconnected-(U1-PA12-Pad33)") (class "Default")
      (node (ref "U1") (pin "33") (pinfunction "PA12_33") (pintype "passive+no_connect"))
    )
    (net (code "76") (name "unconnected-(U1-PB0-Pad18)") (class "Default")
      (node (ref "U1") (pin "18") (pinfunction "PB0_18") (pintype "passive+no_connect"))
    )
    (net (code "77") (name "unconnected-(U1-PB8-Pad45)") (class "Default")
      (node (ref "U1") (pin "45") (pinfunction "PB8_45") (pintype "passive+no_connect"))
    )
    (net (code "78") (name "unconnected-(U1-PB9-Pad46)") (class "Default")
      (node (ref "U1") (pin "46") (pinfunction "PB9_46") (pintype "passive+no_connect"))
    )
    (net (code "79") (name "unconnected-(U1-PB12-Pad25)") (class "Default")
      (node (ref "U1") (pin "25") (pinfunction "PB12_25") (pintype "passive+no_connect"))
    )
    (net (code "80") (name "unconnected-(U1-PB13-Pad26)") (class "Default")
      (node (ref "U1") (pin "26") (pinfunction "PB13_26") (pintype "passive+no_connect"))
    )
    (net (code "81") (name "unconnected-(U1-PB14-Pad27)") (class "Default")
      (node (ref "U1") (pin "27") (pinfunction "PB14_27") (pintype "passive+no_connect"))
    )
    (net (code "82") (name "unconnected-(U1-PB15-Pad28)") (class "Default")
      (node (ref "U1") (pin "28") (pinfunction "PB15_28") (pintype "passive+no_connect"))
    )
    (net (code "83") (name "unconnected-(U1-PC13-Pad2)") (class "Default")
      (node (ref "U1") (pin "2") (pinfunction "PC13_2") (pintype "passive+no_connect"))
    )
    (net (code "84") (name "unconnected-(U1-PC14-OSC32_IN-Pad3)") (class "Default")
      (node (ref "U1") (pin "3") (pinfunction "PC14-OSC32_IN_3") (pintype "passive+no_connect"))
    )
    (net (code "85") (name "unconnected-(U1-PC15-OSC32_OUT-Pad4)") (class "Default")
      (node (ref "U1") (pin "4") (pinfunction "PC15-OSC32_OUT_4") (pintype "passive+no_connect"))
    )
  )
)
